# NetMY.net
KiCad netlist of a schematic drawn in Altium Designer
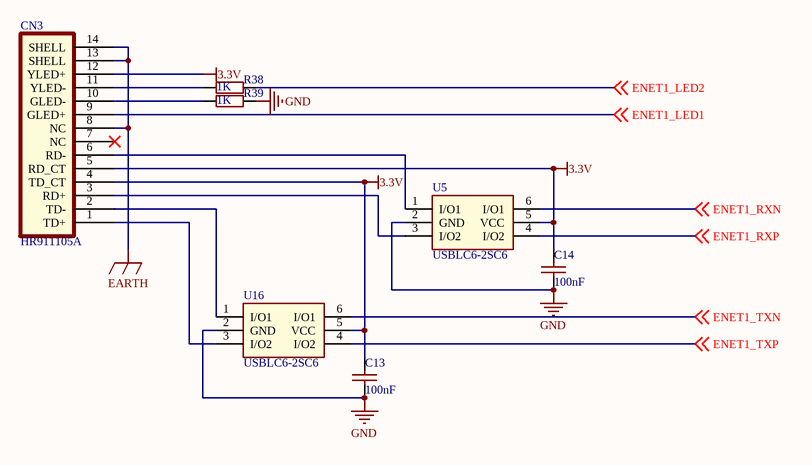
[diagram p0: NetMY.SchDoc]

(export (version "E")
  (design (tool "Eeschema 10.0.6"))
  (components
    (comp (ref "C13")
      (value "100nF")
      (footprint "0805SMD_Cap")
      (description "贴片电容")
      (libsource (lib "ST_GND_Sch") (part "SMD_Cap"))
    )
    (comp (ref "C14")
      (value "100nF")
      (footprint "0805SMD_Cap")
      (description "贴片电容")
      (libsource (lib "ST_GND_Sch") (part "SMD_Cap"))
    )
    (comp (ref "CN3")
      (value "HR911105A")
      (footprint "RJ-45A12")
      (libsource (lib "ST_GND_Sch") (part "HR911105A"))
    )
    (comp (ref "R38")
      (value "1K")
      (footprint "0805_SMD_R")
      (description "贴片电阻")
      (libsource (lib "ST_GND_Sch") (part "SMD_0805"))
    )
    (comp (ref "R39")
      (value "1K")
      (footprint "0805_SMD_R")
      (description "贴片电阻")
      (libsource (lib "ST_GND_Sch") (part "SMD_0805"))
    )
    (comp (ref "U5")
      (value "USBLC6-2SC6")
      (footprint "SOT-23-6")
      (libsource (lib "ST_GND_Sch") (part "USBLC6-2SC6"))
    )
    (comp (ref "U16")
      (value "USBLC6-2SC6")
      (footprint "SOT-23-6")
      (libsource (lib "ST_GND_Sch") (part "USBLC6-2SC6"))
    )
  )
  (nets
    (net (code "1") (name "3.3V") (class "Default")
      (node (ref "C13") (pin "2") (pintype "passive"))
      (node (ref "C14") (pin "2") (pintype "passive"))
      (node (ref "CN3") (pin "12") (pinfunction "YLED+_12") (pintype "passive"))
      (node (ref "CN3") (pin "4") (pinfunction "TD_CT_4") (pintype "passive"))
      (node (ref "CN3") (pin "5") (pinfunction "RD_CT_5") (pintype "passive"))
      (node (ref "U16") (pin "5") (pinfunction "VCC_5") (pintype "passive"))
      (node (ref "U5") (pin "5") (pinfunction "VCC_5") (pintype "passive"))
    )
    (net (code "2") (name "EARTH") (class "Default")
      (node (ref "CN3") (pin "13") (pinfunction "SHELL_13") (pintype "passive"))
      (node (ref "CN3") (pin "14") (pinfunction "SHELL_14") (pintype "passive"))
      (node (ref "CN3") (pin "8") (pinfunction "NC_8") (pintype "passive"))
    )
    (net (code "3") (name "ENET1_LED1") (class "Default")
      (node (ref "CN3") (pin "9") (pinfunction "GLED+_9") (pintype "passive"))
    )
    (net (code "4") (name "ENET1_LED2") (class "Default")
      (node (ref "R38") (pin "2") (pinfunction "2_2") (pintype "passive"))
    )
    (net (code "5") (name "ENET1_RXN") (class "Default")
      (node (ref "U5") (pin "6") (pinfunction "I/O1_6") (pintype "passive"))
    )
    (net (code "6") (name "ENET1_RXP") (class "Default")
      (node (ref "U5") (pin "4") (pinfunction "I/O2_4") (pintype "passive"))
    )
    (net (code "7") (name "ENET1_TXN") (class "Default")
      (node (ref "U16") (pin "6") (pinfunction "I/O1_6") (pintype "passive"))
    )
    (net (code "8") (name "ENET1_TXP") (class "Default")
      (node (ref "U16") (pin "4") (pinfunction "I/O2_4") (pintype "passive"))
    )
    (net (code "9") (name "GND") (class "Default")
      (node (ref "C13") (pin "1") (pintype "passive"))
      (node (ref "C14") (pin "1") (pintype "passive"))
      (node (ref "R39") (pin "2") (pinfunction "2_2") (pintype "passive"))
      (node (ref "U16") (pin "2") (pinfunction "GND_2") (pintype "passive"))
      (node (ref "U5") (pin "2") (pinfunction "GND_2") (pintype "passive"))
    )
    (net (code "10") (name "Net-(CN3-GLED-)") (class "Default")
      (node (ref "CN3") (pin "10") (pinfunction "GLED-_10") (pintype "passive"))
      (node (ref "R39") (pin "1") (pinfunction "1_1") (pintype "passive"))
    )
    (net (code "11") (name "Net-(CN3-RD+)") (class "Default")
      (node (ref "CN3") (pin "3") (pinfunction "RD+_3") (pintype "passive"))
      (node (ref "U5") (pin "3") (pinfunction "I/O2_3") (pintype "passive"))
    )
    (net (code "12") (name "Net-(CN3-RD-)") (class "Default")
      (node (ref "CN3") (pin "6") (pinfunction "RD-_6") (pintype "passive"))
      (node (ref "U5") (pin "1") (pinfunction "I/O1_1") (pintype "passive"))
    )
    (net (code "13") (name "Net-(CN3-TD+)") (class "Default")
      (node (ref "CN3") (pin "1") (pinfunction "TD+_1") (pintype "passive"))
      (node (ref "U16") (pin "3") (pinfunction "I/O2_3") (pintype "passive"))
    )
    (net (code "14") (name "Net-(CN3-TD-)") (class "Default")
      (node (ref "CN3") (pin "2") (pinfunction "TD-_2") (pintype "passive"))
      (node (ref "U16") (pin "1") (pinfunction "I/O1_1") (pintype "passive"))
    )
    (net (code "15") (name "Net-(CN3-YLED-)") (class "Default")
      (node (ref "CN3") (pin "11") (pinfunction "YLED-_11") (pintype "passive"))
      (node (ref "R38") (pin "1") (pinfunction "1_1") (pintype "passive"))
    )
    (net (code "16") (name "unconnected-(CN3-NC-Pad7)") (class "Default")
      (node (ref "CN3") (pin "7") (pinfunction "NC_7") (pintype "passive+no_connect"))
    )
  )
)
